# MCU.net
KiCad netlist of a schematic drawn in Altium Designer
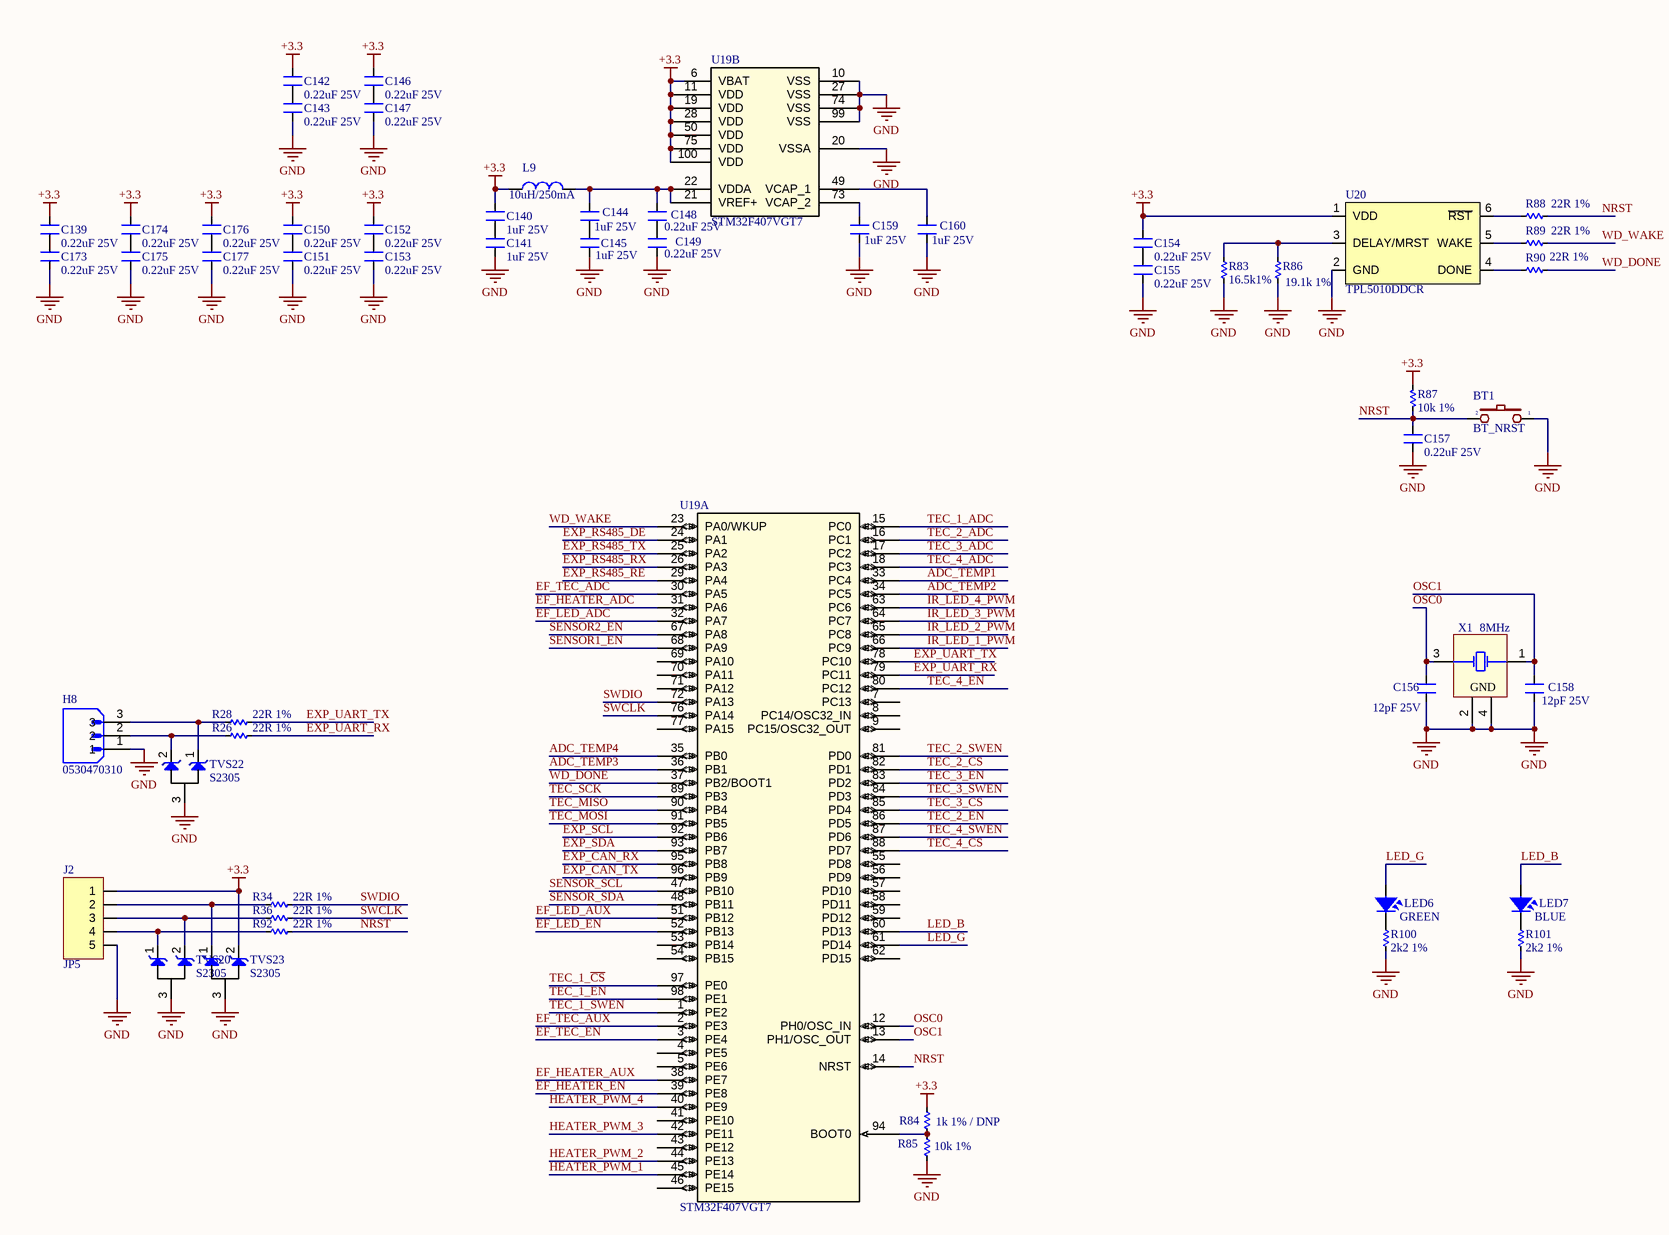
[diagram p0: MCU.SchDoc]

(export (version "E")
  (design (tool "Eeschema 10.0.6"))
  (components
    (comp (ref "BT1")
      (value "BT_NRST")
      (footprint "SW1-SMD")
      (description "Switch button 2 pin")
      (libsource (lib "Sang_library") (part "SW2"))
    )
    (comp (ref "C139")
      (value "0.22uF 25V")
      (footprint "CN-SMD-0603")
      (libsource (lib "Sang_library") (part "Capacitors"))
    )
    (comp (ref "C140")
      (value "1uF 25V")
      (footprint "CN-SMD-0603")
      (libsource (lib "Sang_library") (part "Capacitors"))
    )
    (comp (ref "C141")
      (value "1uF 25V")
      (footprint "CN-SMD-0603")
      (libsource (lib "Sang_library") (part "Capacitors"))
    )
    (comp (ref "C142")
      (value "0.22uF 25V")
      (footprint "CN-SMD-0603")
      (libsource (lib "Sang_library") (part "Capacitors"))
    )
    (comp (ref "C143")
      (value "0.22uF 25V")
      (footprint "CN-SMD-0603")
      (libsource (lib "Sang_library") (part "Capacitors"))
    )
    (comp (ref "C144")
      (value "1uF 25V")
      (footprint "CN-SMD-0603")
      (libsource (lib "Sang_library") (part "Capacitors"))
    )
    (comp (ref "C145")
      (value "1uF 25V")
      (footprint "CN-SMD-0603")
      (libsource (lib "Sang_library") (part "Capacitors"))
    )
    (comp (ref "C146")
      (value "0.22uF 25V")
      (footprint "CN-SMD-0603")
      (libsource (lib "Sang_library") (part "Capacitors"))
    )
    (comp (ref "C147")
      (value "0.22uF 25V")
      (footprint "CN-SMD-0603")
      (libsource (lib "Sang_library") (part "Capacitors"))
    )
    (comp (ref "C148")
      (value "0.22uF 25V")
      (footprint "CN-SMD-0603")
      (libsource (lib "Sang_library") (part "Capacitors"))
    )
    (comp (ref "C149")
      (value "0.22uF 25V")
      (footprint "CN-SMD-0603")
      (libsource (lib "Sang_library") (part "Capacitors"))
    )
    (comp (ref "C150")
      (value "0.22uF 25V")
      (footprint "CN-SMD-0603")
      (libsource (lib "Sang_library") (part "Capacitors"))
    )
    (comp (ref "C151")
      (value "0.22uF 25V")
      (footprint "CN-SMD-0603")
      (libsource (lib "Sang_library") (part "Capacitors"))
    )
    (comp (ref "C152")
      (value "0.22uF 25V")
      (footprint "CN-SMD-0603")
      (libsource (lib "Sang_library") (part "Capacitors"))
    )
    (comp (ref "C153")
      (value "0.22uF 25V")
      (footprint "CN-SMD-0603")
      (libsource (lib "Sang_library") (part "Capacitors"))
    )
    (comp (ref "C154")
      (value "0.22uF 25V")
      (footprint "CN-SMD-0603")
      (libsource (lib "Sang_library") (part "Capacitors"))
    )
    (comp (ref "C155")
      (value "0.22uF 25V")
      (footprint "CN-SMD-0603")
      (libsource (lib "Sang_library") (part "Capacitors"))
    )
    (comp (ref "C156")
      (value "12pF 25V")
      (footprint "CN-SMD-0603")
      (libsource (lib "Sang_library") (part "Capacitors"))
    )
    (comp (ref "C157")
      (value "0.22uF 25V")
      (footprint "CN-SMD-0603")
      (libsource (lib "Sang_library") (part "Capacitors"))
    )
    (comp (ref "C158")
      (value "12pF 25V")
      (footprint "CN-SMD-0603")
      (libsource (lib "Sang_library") (part "Capacitors"))
    )
    (comp (ref "C159")
      (value "1uF 25V")
      (footprint "CN-SMD-0603")
      (libsource (lib "Sang_library") (part "Capacitors"))
    )
    (comp (ref "C160")
      (value "1uF 25V")
      (footprint "CN-SMD-0603")
      (libsource (lib "Sang_library") (part "Capacitors"))
    )
    (comp (ref "C173")
      (value "0.22uF 25V")
      (footprint "CN-SMD-0603")
      (libsource (lib "Sang_library") (part "Capacitors"))
    )
    (comp (ref "C174")
      (value "0.22uF 25V")
      (footprint "CN-SMD-0603")
      (libsource (lib "Sang_library") (part "Capacitors"))
    )
    (comp (ref "C175")
      (value "0.22uF 25V")
      (footprint "CN-SMD-0603")
      (libsource (lib "Sang_library") (part "Capacitors"))
    )
    (comp (ref "C176")
      (value "0.22uF 25V")
      (footprint "CN-SMD-0603")
      (libsource (lib "Sang_library") (part "Capacitors"))
    )
    (comp (ref "C177")
      (value "0.22uF 25V")
      (footprint "CN-SMD-0603")
      (libsource (lib "Sang_library") (part "Capacitors"))
    )
    (comp (ref "H8")
      (value "0530470310")
      (footprint "0530470310")
      (description "CONN HEADER VERT 3POS 1.25MM")
      (libsource (lib "Sang_library") (part "0530470310"))
    )
    (comp (ref "J2")
      (value "JP5")
      (footprint "JP5-D1T")
      (description "WR-PHD 2.54 mm Angled Socket Header")
      (fields
        (field (name "MANUFACTURER") "Würth Elektronik eiSos GmbH")
        (field (name "PARTNO") "613005143121")
        (field (name "CREATED BY") "Karrer Zheng")
      )
      (libsource (lib "Sang_library") (part "JP5"))
    )
    (comp (ref "L9")
      (value "10uH/250mA")
      (footprint "L-SMD-0603")
      (fields
        (field (name "PARTNO") "78477010")
        (field (name "MANUFACTURER") "Wurth Elektronik")
        (field (name "CREATED BY") "Baojun Chen")
      )
      (libsource (lib "Sang_library") (part "L-SMD-1"))
    )
    (comp (ref "LED6")
      (value "GREEN")
      (footprint "LED_0603_RED")
      (libsource (lib "Sang_library") (part "LED SMD"))
    )
    (comp (ref "LED7")
      (value "BLUE")
      (footprint "LED_0603_RED")
      (libsource (lib "Sang_library") (part "LED SMD"))
    )
    (comp (ref "R26")
      (value "22R 1%")
      (footprint "RES-SMD-0603")
      (description "SMD")
      (fields
        (field (name "MANUFACTURER") "Generic Components")
        (field (name "PUBLISHER") "Altium Hobart Technology Centre")
      )
      (libsource (lib "Sang_library") (part "Res SMD"))
    )
    (comp (ref "R28")
      (value "22R 1%")
      (footprint "RES-SMD-0603")
      (description "SMD")
      (fields
        (field (name "MANUFACTURER") "Generic Components")
        (field (name "PUBLISHER") "Altium Hobart Technology Centre")
      )
      (libsource (lib "Sang_library") (part "Res SMD"))
    )
    (comp (ref "R34")
      (value "22R 1%")
      (footprint "RES-SMD-0603")
      (description "SMD")
      (fields
        (field (name "MANUFACTURER") "Generic Components")
        (field (name "PUBLISHER") "Altium Hobart Technology Centre")
      )
      (libsource (lib "Sang_library") (part "Res SMD"))
    )
    (comp (ref "R36")
      (value "22R 1%")
      (footprint "RES-SMD-0603")
      (description "SMD")
      (fields
        (field (name "MANUFACTURER") "Generic Components")
        (field (name "PUBLISHER") "Altium Hobart Technology Centre")
      )
      (libsource (lib "Sang_library") (part "Res SMD"))
    )
    (comp (ref "R83")
      (value "16.5k1%")
      (footprint "RES-SMD-0603")
      (description "SMD")
      (fields
        (field (name "MANUFACTURER") "Generic Components")
        (field (name "PUBLISHER") "Altium Hobart Technology Centre")
      )
      (libsource (lib "Sang_library") (part "Res SMD"))
    )
    (comp (ref "R84")
      (value "1k 1% / DNP")
      (footprint "RES-SMD-0603")
      (description "SMD")
      (fields
        (field (name "MANUFACTURER") "Generic Components")
        (field (name "PUBLISHER") "Altium Hobart Technology Centre")
      )
      (libsource (lib "Sang_library") (part "Res SMD"))
    )
    (comp (ref "R85")
      (value "10k 1%")
      (footprint "RES-SMD-0603")
      (description "SMD")
      (fields
        (field (name "MANUFACTURER") "Generic Components")
        (field (name "PUBLISHER") "Altium Hobart Technology Centre")
      )
      (libsource (lib "Sang_library") (part "Res SMD"))
    )
    (comp (ref "R86")
      (value "19.1k 1%")
      (footprint "RES-SMD-0603")
      (description "SMD")
      (fields
        (field (name "MANUFACTURER") "Generic Components")
        (field (name "PUBLISHER") "Altium Hobart Technology Centre")
      )
      (libsource (lib "Sang_library") (part "Res SMD"))
    )
    (comp (ref "R87")
      (value "10k 1%")
      (footprint "RES-SMD-0603")
      (description "SMD")
      (fields
        (field (name "MANUFACTURER") "Generic Components")
        (field (name "PUBLISHER") "Altium Hobart Technology Centre")
      )
      (libsource (lib "Sang_library") (part "Res SMD"))
    )
    (comp (ref "R88")
      (value "22R 1%")
      (footprint "RES-SMD-0603")
      (description "SMD")
      (fields
        (field (name "MANUFACTURER") "Generic Components")
        (field (name "PUBLISHER") "Altium Hobart Technology Centre")
      )
      (libsource (lib "Sang_library") (part "Res SMD"))
    )
    (comp (ref "R89")
      (value "22R 1%")
      (footprint "RES-SMD-0603")
      (description "SMD")
      (fields
        (field (name "MANUFACTURER") "Generic Components")
        (field (name "PUBLISHER") "Altium Hobart Technology Centre")
      )
      (libsource (lib "Sang_library") (part "Res SMD"))
    )
    (comp (ref "R90")
      (value "22R 1%")
      (footprint "RES-SMD-0603")
      (description "SMD")
      (fields
        (field (name "MANUFACTURER") "Generic Components")
        (field (name "PUBLISHER") "Altium Hobart Technology Centre")
      )
      (libsource (lib "Sang_library") (part "Res SMD"))
    )
    (comp (ref "R92")
      (value "22R 1%")
      (footprint "RES-SMD-0603")
      (description "SMD")
      (fields
        (field (name "MANUFACTURER") "Generic Components")
        (field (name "PUBLISHER") "Altium Hobart Technology Centre")
      )
      (libsource (lib "Sang_library") (part "Res SMD"))
    )
    (comp (ref "R100")
      (value "2k2 1%")
      (footprint "RES-SMD-0603")
      (description "SMD")
      (fields
        (field (name "MANUFACTURER") "Generic Components")
        (field (name "PUBLISHER") "Altium Hobart Technology Centre")
      )
      (libsource (lib "Sang_library") (part "Res SMD"))
    )
    (comp (ref "R101")
      (value "2k2 1%")
      (footprint "RES-SMD-0603")
      (description "SMD")
      (fields
        (field (name "MANUFACTURER") "Generic Components")
        (field (name "PUBLISHER") "Altium Hobart Technology Centre")
      )
      (libsource (lib "Sang_library") (part "Res SMD"))
    )
    (comp (ref "TVS20")
      (value "S2305")
      (footprint "sot23-12_3")
      (description "TVS DIODE 5VWM 10.8VC SOT23")
      (libsource (lib "Sang_library") (part "S2305"))
    )
    (comp (ref "TVS22")
      (value "S2305")
      (footprint "sot23-12_3")
      (description "TVS DIODE 5VWM 10.8VC SOT23")
      (libsource (lib "Sang_library") (part "S2305"))
    )
    (comp (ref "TVS23")
      (value "S2305")
      (footprint "sot23-12_3")
      (description "TVS DIODE 5VWM 10.8VC SOT23")
      (libsource (lib "Sang_library") (part "S2305"))
    )
    (comp (ref "U19")
      (value "STM32F407VGT7")
      (footprint "LQFP-100")
      (libsource (lib "Sang_library") (part "STM32F407VGT7"))
    )
    (comp (ref "U20")
      (value "TPL5010DDCR")
      (footprint "SOT23-6-123_456")
      (description "IC OSC PROG TIMER TSOT23-6")
      (libsource (lib "Sang_library") (part "TPL5010DDCR"))
    )
    (comp (ref "X1")
      (value "8MHz")
      (footprint "XT4-16.000MHz-4_V")
      (description "Crystal, 8 MHz, -30 to 85 degC, 3.2 x 2.5 x 0.9 mm SMD")
      (libsource (lib "Library") (part "XT4"))
    )
  )
  (nets
    (net (code "1") (name "+3.3") (class "Default")
      (node (ref "C139") (pin "2") (pinfunction "2_2") (pintype "passive"))
      (node (ref "C140") (pin "2") (pinfunction "2_2") (pintype "passive"))
      (node (ref "C142") (pin "2") (pinfunction "2_2") (pintype "passive"))
      (node (ref "C146") (pin "2") (pinfunction "2_2") (pintype "passive"))
      (node (ref "C150") (pin "2") (pinfunction "2_2") (pintype "passive"))
      (node (ref "C152") (pin "2") (pinfunction "2_2") (pintype "passive"))
      (node (ref "C154") (pin "2") (pinfunction "2_2") (pintype "passive"))
      (node (ref "C174") (pin "2") (pinfunction "2_2") (pintype "passive"))
      (node (ref "C176") (pin "2") (pinfunction "2_2") (pintype "passive"))
      (node (ref "J2") (pin "1") (pinfunction "1_1") (pintype "passive"))
      (node (ref "L9") (pin "1") (pinfunction "1_1") (pintype "passive"))
      (node (ref "R84") (pin "1") (pinfunction "1_1") (pintype "passive"))
      (node (ref "R87") (pin "1") (pinfunction "1_1") (pintype "passive"))
      (node (ref "TVS23") (pin "2") (pinfunction "2_2") (pintype "passive"))
      (node (ref "U19") (pin "100") (pinfunction "VDD_100") (pintype "power_in"))
      (node (ref "U19") (pin "11") (pinfunction "VDD_11") (pintype "power_in"))
      (node (ref "U19") (pin "19") (pinfunction "VDD_19") (pintype "power_in"))
      (node (ref "U19") (pin "28") (pinfunction "VDD_28") (pintype "power_in"))
      (node (ref "U19") (pin "50") (pinfunction "VDD_50") (pintype "power_in"))
      (node (ref "U19") (pin "6") (pinfunction "VBAT_6") (pintype "power_in"))
      (node (ref "U19") (pin "75") (pinfunction "VDD_75") (pintype "power_in"))
      (node (ref "U20") (pin "1") (pinfunction "VDD_1") (pintype "passive"))
    )
    (net (code "2") (name "/ADC_TEMP1") (class "Default")
      (node (ref "U19") (pin "33") (pinfunction "PC4_33") (pintype "bidirectional"))
    )
    (net (code "3") (name "/ADC_TEMP2") (class "Default")
      (node (ref "U19") (pin "34") (pinfunction "PC5_34") (pintype "bidirectional"))
    )
    (net (code "4") (name "/ADC_TEMP3") (class "Default")
      (node (ref "U19") (pin "36") (pinfunction "PB1_36") (pintype "bidirectional"))
    )
    (net (code "5") (name "/ADC_TEMP4") (class "Default")
      (node (ref "U19") (pin "35") (pinfunction "PB0_35") (pintype "bidirectional"))
    )
    (net (code "6") (name "/EF_HEATER_ADC") (class "Default")
      (node (ref "U19") (pin "31") (pinfunction "PA6_31") (pintype "bidirectional"))
    )
    (net (code "7") (name "/EF_HEATER_AUX") (class "Default")
      (node (ref "U19") (pin "38") (pinfunction "PE7_38") (pintype "bidirectional"))
    )
    (net (code "8") (name "/EF_HEATER_EN") (class "Default")
      (node (ref "U19") (pin "39") (pinfunction "PE8_39") (pintype "bidirectional"))
    )
    (net (code "9") (name "/EF_LED_ADC") (class "Default")
      (node (ref "U19") (pin "32") (pinfunction "PA7_32") (pintype "bidirectional"))
    )
    (net (code "10") (name "/EF_LED_AUX") (class "Default")
      (node (ref "U19") (pin "51") (pinfunction "PB12_51") (pintype "bidirectional"))
    )
    (net (code "11") (name "/EF_LED_EN") (class "Default")
      (node (ref "U19") (pin "52") (pinfunction "PB13_52") (pintype "bidirectional"))
    )
    (net (code "12") (name "/EF_TEC_ADC") (class "Default")
      (node (ref "U19") (pin "30") (pinfunction "PA5_30") (pintype "bidirectional"))
    )
    (net (code "13") (name "/EF_TEC_AUX") (class "Default")
      (node (ref "U19") (pin "2") (pinfunction "PE3_2") (pintype "bidirectional"))
    )
    (net (code "14") (name "/EF_TEC_EN") (class "Default")
      (node (ref "U19") (pin "3") (pinfunction "PE4_3") (pintype "bidirectional"))
    )
    (net (code "15") (name "/EXP_CAN_RX") (class "Default")
      (node (ref "U19") (pin "95") (pinfunction "PB8_95") (pintype "bidirectional"))
    )
    (net (code "16") (name "/EXP_CAN_TX") (class "Default")
      (node (ref "U19") (pin "96") (pinfunction "PB9_96") (pintype "bidirectional"))
    )
    (net (code "17") (name "/EXP_RS485_DE") (class "Default")
      (node (ref "U19") (pin "24") (pinfunction "PA1_24") (pintype "bidirectional"))
    )
    (net (code "18") (name "/EXP_RS485_RX") (class "Default")
      (node (ref "U19") (pin "26") (pinfunction "PA3_26") (pintype "bidirectional"))
    )
    (net (code "19") (name "/EXP_RS485_TX") (class "Default")
      (node (ref "U19") (pin "25") (pinfunction "PA2_25") (pintype "bidirectional"))
    )
    (net (code "20") (name "/EXP_RS485_~{RE}") (class "Default")
      (node (ref "U19") (pin "29") (pinfunction "PA4_29") (pintype "bidirectional"))
    )
    (net (code "21") (name "/EXP_SCL") (class "Default")
      (node (ref "U19") (pin "92") (pinfunction "PB6_92") (pintype "bidirectional"))
    )
    (net (code "22") (name "/EXP_SDA") (class "Default")
      (node (ref "U19") (pin "93") (pinfunction "PB7_93") (pintype "bidirectional"))
    )
    (net (code "23") (name "/EXP_UART_RX") (class "Default")
      (node (ref "R26") (pin "1") (pinfunction "1_1") (pintype "passive"))
      (node (ref "U19") (pin "79") (pinfunction "PC11_79") (pintype "bidirectional"))
    )
    (net (code "24") (name "/EXP_UART_TX") (class "Default")
      (node (ref "R28") (pin "1") (pinfunction "1_1") (pintype "passive"))
      (node (ref "U19") (pin "78") (pinfunction "PC10_78") (pintype "bidirectional"))
    )
    (net (code "25") (name "/HEATER_PWM_1") (class "Default")
      (node (ref "U19") (pin "45") (pinfunction "PE14_45") (pintype "bidirectional"))
    )
    (net (code "26") (name "/HEATER_PWM_2") (class "Default")
      (node (ref "U19") (pin "44") (pinfunction "PE13_44") (pintype "bidirectional"))
    )
    (net (code "27") (name "/HEATER_PWM_3") (class "Default")
      (node (ref "U19") (pin "42") (pinfunction "PE11_42") (pintype "bidirectional"))
    )
    (net (code "28") (name "/HEATER_PWM_4") (class "Default")
      (node (ref "U19") (pin "40") (pinfunction "PE9_40") (pintype "bidirectional"))
    )
    (net (code "29") (name "/IR_LED_1_PWM") (class "Default")
      (node (ref "U19") (pin "66") (pinfunction "PC9_66") (pintype "bidirectional"))
    )
    (net (code "30") (name "/IR_LED_2_PWM") (class "Default")
      (node (ref "U19") (pin "65") (pinfunction "PC8_65") (pintype "bidirectional"))
    )
    (net (code "31") (name "/IR_LED_3_PWM") (class "Default")
      (node (ref "U19") (pin "64") (pinfunction "PC7_64") (pintype "bidirectional"))
    )
    (net (code "32") (name "/IR_LED_4_PWM") (class "Default")
      (node (ref "U19") (pin "63") (pinfunction "PC6_63") (pintype "bidirectional"))
    )
    (net (code "33") (name "/LED_B") (class "Default")
      (node (ref "LED7") (pin "1") (pinfunction "1_1") (pintype "passive"))
      (node (ref "U19") (pin "60") (pinfunction "PD13_60") (pintype "bidirectional"))
    )
    (net (code "34") (name "/LED_G") (class "Default")
      (node (ref "LED6") (pin "1") (pinfunction "1_1") (pintype "passive"))
      (node (ref "U19") (pin "61") (pinfunction "PD14_61") (pintype "bidirectional"))
    )
    (net (code "35") (name "/NRST") (class "Default")
      (node (ref "BT1") (pin "2") (pinfunction "2_2") (pintype "passive"))
      (node (ref "C157") (pin "2") (pinfunction "2_2") (pintype "passive"))
      (node (ref "R87") (pin "2") (pinfunction "2_2") (pintype "passive"))
      (node (ref "R88") (pin "2") (pinfunction "2_2") (pintype "passive"))
      (node (ref "R92") (pin "1") (pinfunction "1_1") (pintype "passive"))
      (node (ref "U19") (pin "14") (pinfunction "NRST_14") (pintype "bidirectional"))
    )
    (net (code "36") (name "/OSC0") (class "Default")
      (node (ref "C156") (pin "1") (pinfunction "1_1") (pintype "passive"))
      (node (ref "U19") (pin "12") (pinfunction "PH0/OSC_IN_12") (pintype "bidirectional"))
      (node (ref "X1") (pin "3") (pinfunction "XTAL_3") (pintype "passive"))
    )
    (net (code "37") (name "/OSC1") (class "Default")
      (node (ref "C158") (pin "2") (pinfunction "2_2") (pintype "passive"))
      (node (ref "U19") (pin "13") (pinfunction "PH1/OSC_OUT_13") (pintype "bidirectional"))
      (node (ref "X1") (pin "1") (pinfunction "XTAL_1") (pintype "passive"))
    )
    (net (code "38") (name "/SENSOR1_EN") (class "Default")
      (node (ref "U19") (pin "68") (pinfunction "PA9_68") (pintype "bidirectional"))
    )
    (net (code "39") (name "/SENSOR2_EN") (class "Default")
      (node (ref "U19") (pin "67") (pinfunction "PA8_67") (pintype "bidirectional"))
    )
    (net (code "40") (name "/SENSOR_SCL") (class "Default")
      (node (ref "U19") (pin "47") (pinfunction "PB10_47") (pintype "bidirectional"))
    )
    (net (code "41") (name "/SENSOR_SDA") (class "Default")
      (node (ref "U19") (pin "48") (pinfunction "PB11_48") (pintype "bidirectional"))
    )
    (net (code "42") (name "/SWCLK") (class "Default")
      (node (ref "R36") (pin "1") (pinfunction "1_1") (pintype "passive"))
      (node (ref "U19") (pin "76") (pinfunction "PA14_76") (pintype "bidirectional"))
    )
    (net (code "43") (name "/SWDIO") (class "Default")
      (node (ref "R34") (pin "1") (pinfunction "1_1") (pintype "passive"))
      (node (ref "U19") (pin "72") (pinfunction "PA13_72") (pintype "bidirectional"))
    )
    (net (code "44") (name "/TEC_1_ADC") (class "Default")
      (node (ref "U19") (pin "15") (pinfunction "PC0_15") (pintype "bidirectional"))
    )
    (net (code "45") (name "/TEC_1_EN") (class "Default")
      (node (ref "U19") (pin "98") (pinfunction "PE1_98") (pintype "bidirectional"))
    )
    (net (code "46") (name "/TEC_1_SWEN") (class "Default")
      (node (ref "U19") (pin "1") (pinfunction "PE2_1") (pintype "bidirectional"))
    )
    (net (code "47") (name "/TEC_1_~{CS}") (class "Default")
      (node (ref "U19") (pin "97") (pinfunction "PE0_97") (pintype "bidirectional"))
    )
    (net (code "48") (name "/TEC_2_ADC") (class "Default")
      (node (ref "U19") (pin "16") (pinfunction "PC1_16") (pintype "bidirectional"))
    )
    (net (code "49") (name "/TEC_2_EN") (class "Default")
      (node (ref "U19") (pin "86") (pinfunction "PD5_86") (pintype "bidirectional"))
    )
    (net (code "50") (name "/TEC_2_SWEN") (class "Default")
      (node (ref "U19") (pin "81") (pinfunction "PD0_81") (pintype "bidirectional"))
    )
    (net (code "51") (name "/TEC_2_~{CS}") (class "Default")
      (node (ref "U19") (pin "82") (pinfunction "PD1_82") (pintype "bidirectional"))
    )
    (net (code "52") (name "/TEC_3_ADC") (class "Default")
      (node (ref "U19") (pin "17") (pinfunction "PC2_17") (pintype "bidirectional"))
    )
    (net (code "53") (name "/TEC_3_EN") (class "Default")
      (node (ref "U19") (pin "83") (pinfunction "PD2_83") (pintype "bidirectional"))
    )
    (net (code "54") (name "/TEC_3_SWEN") (class "Default")
      (node (ref "U19") (pin "84") (pinfunction "PD3_84") (pintype "bidirectional"))
    )
    (net (code "55") (name "/TEC_3_~{CS}") (class "Default")
      (node (ref "U19") (pin "85") (pinfunction "PD4_85") (pintype "bidirectional"))
    )
    (net (code "56") (name "/TEC_4_ADC") (class "Default")
      (node (ref "U19") (pin "18") (pinfunction "PC3_18") (pintype "bidirectional"))
    )
    (net (code "57") (name "/TEC_4_EN") (class "Default")
      (node (ref "U19") (pin "80") (pinfunction "PC12_80") (pintype "bidirectional"))
    )
    (net (code "58") (name "/TEC_4_SWEN") (class "Default")
      (node (ref "U19") (pin "87") (pinfunction "PD6_87") (pintype "bidirectional"))
    )
    (net (code "59") (name "/TEC_4_~{CS}") (class "Default")
      (node (ref "U19") (pin "88") (pinfunction "PD7_88") (pintype "bidirectional"))
    )
    (net (code "60") (name "/TEC_MISO") (class "Default")
      (node (ref "U19") (pin "90") (pinfunction "PB4_90") (pintype "bidirectional"))
    )
    (net (code "61") (name "/TEC_MOSI") (class "Default")
      (node (ref "U19") (pin "91") (pinfunction "PB5_91") (pintype "bidirectional"))
    )
    (net (code "62") (name "/TEC_SCK") (class "Default")
      (node (ref "U19") (pin "89") (pinfunction "PB3_89") (pintype "bidirectional"))
    )
    (net (code "63") (name "/WD_DONE") (class "Default")
      (node (ref "R90") (pin "2") (pinfunction "2_2") (pintype "passive"))
      (node (ref "U19") (pin "37") (pinfunction "PB2/BOOT1_37") (pintype "bidirectional"))
    )
    (net (code "64") (name "/WD_WAKE") (class "Default")
      (node (ref "R89") (pin "2") (pinfunction "2_2") (pintype "passive"))
      (node (ref "U19") (pin "23") (pinfunction "PA0/WKUP_23") (pintype "bidirectional"))
    )
    (net (code "65") (name "GND") (class "Default")
      (node (ref "BT1") (pin "1") (pinfunction "1_1") (pintype "passive"))
      (node (ref "C141") (pin "1") (pinfunction "1_1") (pintype "passive"))
      (node (ref "C143") (pin "1") (pinfunction "1_1") (pintype "passive"))
      (node (ref "C145") (pin "1") (pinfunction "1_1") (pintype "passive"))
      (node (ref "C147") (pin "1") (pinfunction "1_1") (pintype "passive"))
      (node (ref "C149") (pin "1") (pinfunction "1_1") (pintype "passive"))
      (node (ref "C151") (pin "1") (pinfunction "1_1") (pintype "passive"))
      (node (ref "C153") (pin "1") (pinfunction "1_1") (pintype "passive"))
      (node (ref "C155") (pin "1") (pinfunction "1_1") (pintype "passive"))
      (node (ref "C156") (pin "2") (pinfunction "2_2") (pintype "passive"))
      (node (ref "C157") (pin "1") (pinfunction "1_1") (pintype "passive"))
      (node (ref "C158") (pin "1") (pinfunction "1_1") (pintype "passive"))
      (node (ref "C159") (pin "1") (pinfunction "1_1") (pintype "passive"))
      (node (ref "C160") (pin "1") (pinfunction "1_1") (pintype "passive"))
      (node (ref "C173") (pin "1") (pinfunction "1_1") (pintype "passive"))
      (node (ref "C175") (pin "1") (pinfunction "1_1") (pintype "passive"))
      (node (ref "C177") (pin "1") (pinfunction "1_1") (pintype "passive"))
      (node (ref "H8") (pin "1") (pinfunction "1_1") (pintype "passive"))
      (node (ref "J2") (pin "5") (pinfunction "5_5") (pintype "passive"))
      (node (ref "R100") (pin "2") (pinfunction "2_2") (pintype "passive"))
      (node (ref "R101") (pin "2") (pinfunction "2_2") (pintype "passive"))
      (node (ref "R83") (pin "1") (pinfunction "1_1") (pintype "passive"))
      (node (ref "R85") (pin "2") (pinfunction "2_2") (pintype "passive"))
      (node (ref "R86") (pin "1") (pinfunction "1_1") (pintype "passive"))
      (node (ref "TVS20") (pin "3") (pinfunction "3_3") (pintype "passive"))
      (node (ref "TVS22") (pin "3") (pinfunction "3_3") (pintype "passive"))
      (node (ref "TVS23") (pin "3") (pinfunction "3_3") (pintype "passive"))
      (node (ref "U19") (pin "10") (pinfunction "VSS_10") (pintype "power_in"))
      (node (ref "U19") (pin "20") (pinfunction "VSSA_20") (pintype "power_in"))
      (node (ref "U19") (pin "27") (pinfunction "VSS_27") (pintype "power_in"))
      (node (ref "U19") (pin "74") (pinfunction "VSS_74") (pintype "power_in"))
      (node (ref "U19") (pin "99") (pinfunction "VSS_99") (pintype "power_in"))
      (node (ref "U20") (pin "2") (pinfunction "GND_2") (pintype "passive"))
      (node (ref "X1") (pin "2") (pinfunction "GND_2") (pintype "power_in"))
      (node (ref "X1") (pin "4") (pinfunction "GND_4") (pintype "power_in"))
    )
    (net (code "66") (name "Net-(C139-Pad1)") (class "Default")
      (node (ref "C139") (pin "1") (pinfunction "1_1") (pintype "passive"))
      (node (ref "C173") (pin "2") (pinfunction "2_2") (pintype "passive"))
    )
    (net (code "67") (name "Net-(C140-Pad1)") (class "Default")
      (node (ref "C140") (pin "1") (pinfunction "1_1") (pintype "passive"))
      (node (ref "C141") (pin "2") (pinfunction "2_2") (pintype "passive"))
    )
    (net (code "68") (name "Net-(C142-Pad1)") (class "Default")
      (node (ref "C142") (pin "1") (pinfunction "1_1") (pintype "passive"))
      (node (ref "C143") (pin "2") (pinfunction "2_2") (pintype "passive"))
    )
    (net (code "69") (name "Net-(C144-Pad1)") (class "Default")
      (node (ref "C144") (pin "1") (pinfunction "1_1") (pintype "passive"))
      (node (ref "C145") (pin "2") (pinfunction "2_2") (pintype "passive"))
    )
    (net (code "70") (name "Net-(C146-Pad1)") (class "Default")
      (node (ref "C146") (pin "1") (pinfunction "1_1") (pintype "passive"))
      (node (ref "C147") (pin "2") (pinfunction "2_2") (pintype "passive"))
    )
    (net (code "71") (name "Net-(C148-Pad1)") (class "Default")
      (node (ref "C148") (pin "1") (pinfunction "1_1") (pintype "passive"))
      (node (ref "C149") (pin "2") (pinfunction "2_2") (pintype "passive"))
    )
    (net (code "72") (name "Net-(C150-Pad1)") (class "Default")
      (node (ref "C150") (pin "1") (pinfunction "1_1") (pintype "passive"))
      (node (ref "C151") (pin "2") (pinfunction "2_2") (pintype "passive"))
    )
    (net (code "73") (name "Net-(C152-Pad1)") (class "Default")
      (node (ref "C152") (pin "1") (pinfunction "1_1") (pintype "passive"))
      (node (ref "C153") (pin "2") (pinfunction "2_2") (pintype "passive"))
    )
    (net (code "74") (name "Net-(C154-Pad1)") (class "Default")
      (node (ref "C154") (pin "1") (pinfunction "1_1") (pintype "passive"))
      (node (ref "C155") (pin "2") (pinfunction "2_2") (pintype "passive"))
    )
    (net (code "75") (name "Net-(C174-Pad1)") (class "Default")
      (node (ref "C174") (pin "1") (pinfunction "1_1") (pintype "passive"))
      (node (ref "C175") (pin "2") (pinfunction "2_2") (pintype "passive"))
    )
    (net (code "76") (name "Net-(C176-Pad1)") (class "Default")
      (node (ref "C176") (pin "1") (pinfunction "1_1") (pintype "passive"))
      (node (ref "C177") (pin "2") (pinfunction "2_2") (pintype "passive"))
    )
    (net (code "77") (name "Net-(H8-Pad2)") (class "Default")
      (node (ref "H8") (pin "2") (pinfunction "2_2") (pintype "passive"))
      (node (ref "R26") (pin "2") (pinfunction "2_2") (pintype "passive"))
      (node (ref "TVS22") (pin "2") (pinfunction "2_2") (pintype "passive"))
    )
    (net (code "78") (name "Net-(H8-Pad3)") (class "Default")
      (node (ref "H8") (pin "3") (pinfunction "3_3") (pintype "passive"))
      (node (ref "R28") (pin "2") (pinfunction "2_2") (pintype "passive"))
      (node (ref "TVS22") (pin "1") (pinfunction "1_1") (pintype "passive"))
    )
    (net (code "79") (name "Net-(J2-Pad2)") (class "Default")
      (node (ref "J2") (pin "2") (pinfunction "2_2") (pintype "passive"))
      (node (ref "R34") (pin "2") (pinfunction "2_2") (pintype "passive"))
      (node (ref "TVS23") (pin "1") (pinfunction "1_1") (pintype "passive"))
    )
    (net (code "80") (name "Net-(J2-Pad3)") (class "Default")
      (node (ref "J2") (pin "3") (pinfunction "3_3") (pintype "passive"))
      (node (ref "R36") (pin "2") (pinfunction "2_2") (pintype "passive"))
      (node (ref "TVS20") (pin "2") (pinfunction "2_2") (pintype "passive"))
    )
    (net (code "81") (name "Net-(J2-Pad4)") (class "Default")
      (node (ref "J2") (pin "4") (pinfunction "4_4") (pintype "passive"))
      (node (ref "R92") (pin "2") (pinfunction "2_2") (pintype "passive"))
      (node (ref "TVS20") (pin "1") (pinfunction "1_1") (pintype "passive"))
    )
    (net (code "82") (name "Net-(LED6-Pad2)") (class "Default")
      (node (ref "LED6") (pin "2") (pinfunction "2_2") (pintype "passive"))
      (node (ref "R100") (pin "1") (pinfunction "1_1") (pintype "passive"))
    )
    (net (code "83") (name "Net-(LED7-Pad2)") (class "Default")
      (node (ref "LED7") (pin "2") (pinfunction "2_2") (pintype "passive"))
      (node (ref "R101") (pin "1") (pinfunction "1_1") (pintype "passive"))
    )
    (net (code "84") (name "Net-(U19A-BOOT0)") (class "Default")
      (node (ref "R84") (pin "2") (pinfunction "2_2") (pintype "passive"))
      (node (ref "R85") (pin "1") (pinfunction "1_1") (pintype "passive"))
      (node (ref "U19") (pin "94") (pinfunction "BOOT0_94") (pintype "input"))
    )
    (net (code "85") (name "Net-(U19B-VCAP_1)") (class "Default")
      (node (ref "C160") (pin "2") (pinfunction "2_2") (pintype "passive"))
      (node (ref "U19") (pin "49") (pinfunction "VCAP_1_49") (pintype "power_in"))
    )
    (net (code "86") (name "Net-(U19B-VCAP_2)") (class "Default")
      (node (ref "C159") (pin "2") (pinfunction "2_2") (pintype "passive"))
      (node (ref "U19") (pin "73") (pinfunction "VCAP_2_73") (pintype "power_in"))
    )
    (net (code "87") (name "Net-(U19B-VDDA)") (class "Default")
      (node (ref "C144") (pin "2") (pinfunction "2_2") (pintype "passive"))
      (node (ref "C148") (pin "2") (pinfunction "2_2") (pintype "passive"))
      (node (ref "L9") (pin "2") (pinfunction "2_2") (pintype "passive"))
      (node (ref "U19") (pin "21") (pinfunction "VREF+_21") (pintype "power_in"))
      (node (ref "U19") (pin "22") (pinfunction "VDDA_22") (pintype "power_in"))
    )
    (net (code "88") (name "Net-(U20-DELAY{slash}MRST)") (class "Default")
      (node (ref "R83") (pin "2") (pinfunction "2_2") (pintype "passive"))
      (node (ref "R86") (pin "2") (pinfunction "2_2") (pintype "passive"))
      (node (ref "U20") (pin "3") (pinfunction "DELAY/MRST_3") (pintype "passive"))
    )
    (net (code "89") (name "Net-(U20-DONE)") (class "Default")
      (node (ref "R90") (pin "1") (pinfunction "1_1") (pintype "passive"))
      (node (ref "U20") (pin "4") (pinfunction "DONE_4") (pintype "passive"))
    )
    (net (code "90") (name "Net-(U20-WAKE)") (class "Default")
      (node (ref "R89") (pin "1") (pinfunction "1_1") (pintype "passive"))
      (node (ref "U20") (pin "5") (pinfunction "WAKE_5") (pintype "passive"))
    )
    (net (code "91") (name "Net-(U20-~{RST})") (class "Default")
      (node (ref "R88") (pin "1") (pinfunction "1_1") (pintype "passive"))
      (node (ref "U20") (pin "6") (pinfunction "~{RST}_6") (pintype "passive"))
    )
    (net (code "92") (name "unconnected-(U19A-PA10-Pad69)") (class "Default")
      (node (ref "U19") (pin "69") (pinfunction "PA10_69") (pintype "bidirectional"))
    )
    (net (code "93") (name "unconnected-(U19A-PA11-Pad70)") (class "Default")
      (node (ref "U19") (pin "70") (pinfunction "PA11_70") (pintype "bidirectional"))
    )
    (net (code "94") (name "unconnected-(U19A-PA12-Pad71)") (class "Default")
      (node (ref "U19") (pin "71") (pinfunction "PA12_71") (pintype "bidirectional"))
    )
    (net (code "95") (name "unconnected-(U19A-PA15-Pad77)") (class "Default")
      (node (ref "U19") (pin "77") (pinfunction "PA15_77") (pintype "bidirectional"))
    )
    (net (code "96") (name "unconnected-(U19A-PB14-Pad53)") (class "Default")
      (node (ref "U19") (pin "53") (pinfunction "PB14_53") (pintype "bidirectional"))
    )
    (net (code "97") (name "unconnected-(U19A-PB15-Pad54)") (class "Default")
      (node (ref "U19") (pin "54") (pinfunction "PB15_54") (pintype "bidirectional"))
    )
    (net (code "98") (name "unconnected-(U19A-PC13-Pad7)") (class "Default")
      (node (ref "U19") (pin "7") (pinfunction "PC13_7") (pintype "bidirectional"))
    )
    (net (code "99") (name "unconnected-(U19A-PC14{slash}OSC32_IN-Pad8)") (class "Default")
      (node (ref "U19") (pin "8") (pinfunction "PC14/OSC32_IN_8") (pintype "bidirectional"))
    )
    (net (code "100") (name "unconnected-(U19A-PC15{slash}OSC32_OUT-Pad9)") (class "Default")
      (node (ref "U19") (pin "9") (pinfunction "PC15/OSC32_OUT_9") (pintype "bidirectional"))
    )
    (net (code "101") (name "unconnected-(U19A-PD8-Pad55)") (class "Default")
      (node (ref "U19") (pin "55") (pinfunction "PD8_55") (pintype "bidirectional"))
    )
    (net (code "102") (name "unconnected-(U19A-PD9-Pad56)") (class "Default")
      (node (ref "U19") (pin "56") (pinfunction "PD9_56") (pintype "bidirectional"))
    )
    (net (code "103") (name "unconnected-(U19A-PD10-Pad57)") (class "Default")
      (node (ref "U19") (pin "57") (pinfunction "PD10_57") (pintype "bidirectional"))
    )
    (net (code "104") (name "unconnected-(U19A-PD11-Pad58)") (class "Default")
      (node (ref "U19") (pin "58") (pinfunction "PD11_58") (pintype "bidirectional"))
    )
    (net (code "105") (name "unconnected-(U19A-PD12-Pad59)") (class "Default")
      (node (ref "U19") (pin "59") (pinfunction "PD12_59") (pintype "bidirectional"))
    )
    (net (code "106") (name "unconnected-(U19A-PD15-Pad62)") (class "Default")
      (node (ref "U19") (pin "62") (pinfunction "PD15_62") (pintype "bidirectional"))
    )
    (net (code "107") (name "unconnected-(U19A-PE5-Pad4)") (class "Default")
      (node (ref "U19") (pin "4") (pinfunction "PE5_4") (pintype "bidirectional"))
    )
    (net (code "108") (name "unconnected-(U19A-PE6-Pad5)") (class "Default")
      (node (ref "U19") (pin "5") (pinfunction "PE6_5") (pintype "bidirectional"))
    )
    (net (code "109") (name "unconnected-(U19A-PE10-Pad41)") (class "Default")
      (node (ref "U19") (pin "41") (pinfunction "PE10_41") (pintype "bidirectional"))
    )
    (net (code "110") (name "unconnected-(U19A-PE12-Pad43)") (class "Default")
      (node (ref "U19") (pin "43") (pinfunction "PE12_43") (pintype "bidirectional"))
    )
    (net (code "111") (name "unconnected-(U19A-PE15-Pad46)") (class "Default")
      (node (ref "U19") (pin "46") (pinfunction "PE15_46") (pintype "bidirectional"))
    )
  )
)
